# lab3.net
KiCad netlist of a schematic drawn in EAGLE
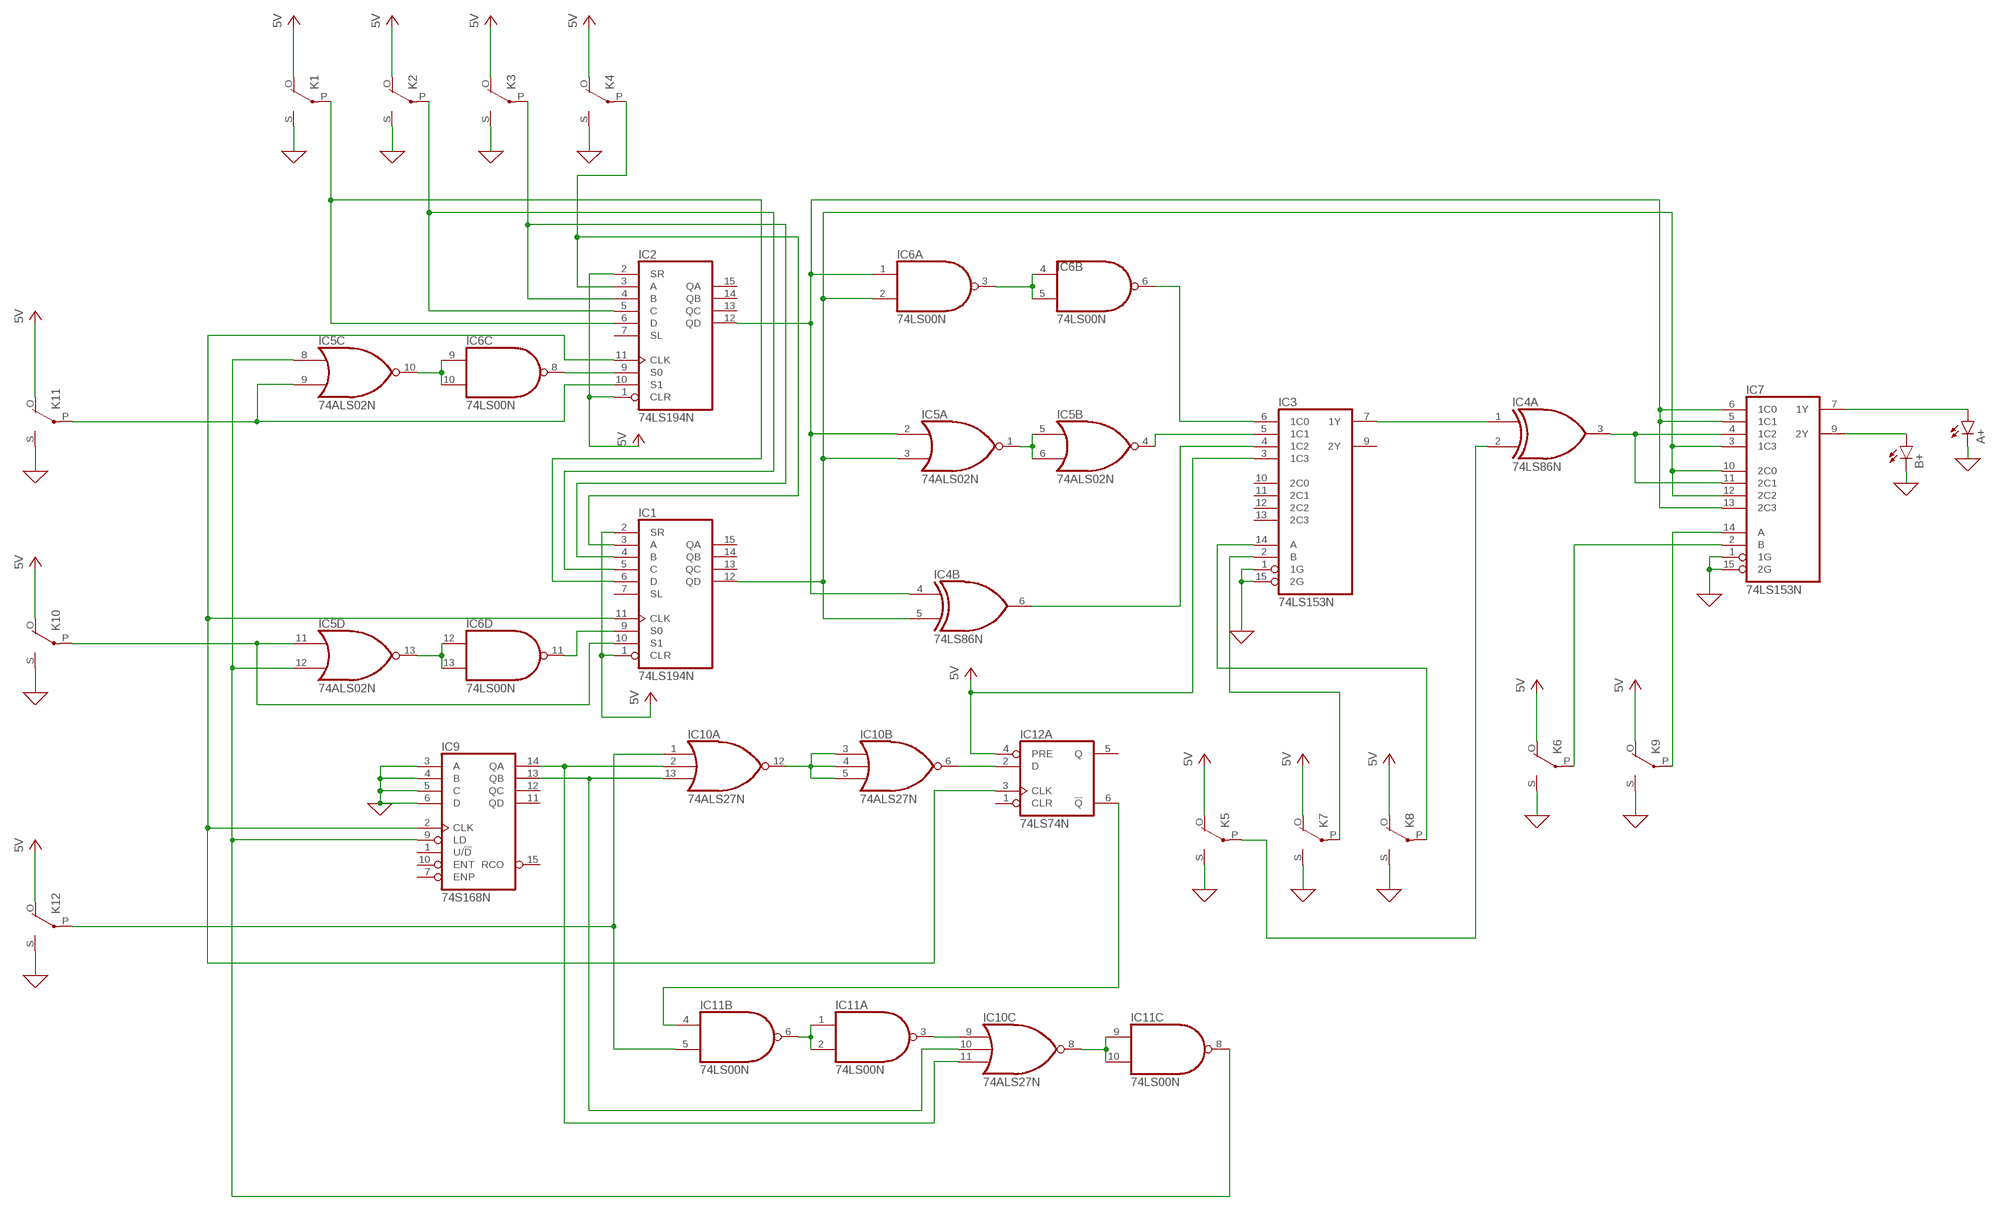
[diagram p0: schematic, sheet 1]

(export (version "E")
  (design (tool "Eeschema 10.0.6"))
  (components
    (comp (ref "A+")
      (value "LED3MM")
      (footprint "eagle-import:LED3MM")
      (libsource (lib "eagle-import") (part "LED3MM"))
    )
    (comp (ref "B+")
      (value "LED3MM")
      (footprint "eagle-import:LED3MM")
      (libsource (lib "eagle-import") (part "LED3MM"))
    )
    (comp (ref "IC1")
      (value "74LS194N")
      (footprint "eagle-import:DIL16")
      (libsource (lib "eagle-import") (part "74194NLS"))
    )
    (comp (ref "IC2")
      (value "74LS194N")
      (footprint "eagle-import:DIL16")
      (libsource (lib "eagle-import") (part "74194NLS"))
    )
    (comp (ref "IC3")
      (value "74LS153N")
      (footprint "eagle-import:DIL16")
      (libsource (lib "eagle-import") (part "74153NLS"))
    )
    (comp (ref "IC4")
      (value "74LS86N")
      (footprint "eagle-import:DIL14")
      (libsource (lib "eagle-import") (part "7486NLS"))
    )
    (comp (ref "IC5")
      (value "74ALS02N")
      (footprint "eagle-import:DIL14")
      (libsource (lib "eagle-import") (part "7402NALS"))
    )
    (comp (ref "IC6")
      (value "74LS00N")
      (footprint "eagle-import:DIL14")
      (libsource (lib "eagle-import") (part "7400NLS"))
    )
    (comp (ref "IC7")
      (value "74LS153N")
      (footprint "eagle-import:DIL16")
      (libsource (lib "eagle-import") (part "74153NLS"))
    )
    (comp (ref "IC9")
      (value "74S168N")
      (footprint "eagle-import:DIL16")
      (libsource (lib "eagle-import") (part "74168NS"))
    )
    (comp (ref "IC10")
      (value "74ALS27N")
      (footprint "eagle-import:DIL14")
      (libsource (lib "eagle-import") (part "7427NALS"))
    )
    (comp (ref "IC11")
      (value "74LS00N")
      (footprint "eagle-import:DIL14")
      (libsource (lib "eagle-import") (part "7400NLS"))
    )
    (comp (ref "IC12")
      (value "74LS74N")
      (footprint "eagle-import:DIL14")
      (libsource (lib "eagle-import") (part "7474NLS"))
    )
    (comp (ref "K1")
      (value "E3206L")
      (footprint "eagle-import:E3206L")
      (libsource (lib "eagle-import") (part "E3206L"))
    )
    (comp (ref "K2")
      (value "E3206L")
      (footprint "eagle-import:E3206L")
      (libsource (lib "eagle-import") (part "E3206L"))
    )
    (comp (ref "K3")
      (value "E3206L")
      (footprint "eagle-import:E3206L")
      (libsource (lib "eagle-import") (part "E3206L"))
    )
    (comp (ref "K4")
      (value "E3206L")
      (footprint "eagle-import:E3206L")
      (libsource (lib "eagle-import") (part "E3206L"))
    )
    (comp (ref "K5")
      (value "E3206L")
      (footprint "eagle-import:E3206L")
      (libsource (lib "eagle-import") (part "E3206L"))
    )
    (comp (ref "K6")
      (value "E3206L")
      (footprint "eagle-import:E3206L")
      (libsource (lib "eagle-import") (part "E3206L"))
    )
    (comp (ref "K7")
      (value "E3206L")
      (footprint "eagle-import:E3206L")
      (libsource (lib "eagle-import") (part "E3206L"))
    )
    (comp (ref "K8")
      (value "E3206L")
      (footprint "eagle-import:E3206L")
      (libsource (lib "eagle-import") (part "E3206L"))
    )
    (comp (ref "K9")
      (value "E3206L")
      (footprint "eagle-import:E3206L")
      (libsource (lib "eagle-import") (part "E3206L"))
    )
    (comp (ref "K10")
      (value "E3206L")
      (footprint "eagle-import:E3206L")
      (libsource (lib "eagle-import") (part "E3206L"))
    )
    (comp (ref "K11")
      (value "E3206L")
      (footprint "eagle-import:E3206L")
      (libsource (lib "eagle-import") (part "E3206L"))
    )
    (comp (ref "K12")
      (value "E3206L")
      (footprint "eagle-import:E3206L")
      (libsource (lib "eagle-import") (part "E3206L"))
    )
  )
  (nets
    (net (code "1") (name "5V") (class "Default")
      (node (ref "IC1") (pin "1") (pinfunction "CLR_1") (pintype "input"))
      (node (ref "IC1") (pin "2") (pinfunction "SR_2") (pintype "input"))
      (node (ref "IC12") (pin "4") (pinfunction "PRE_4") (pintype "input"))
      (node (ref "IC2") (pin "1") (pinfunction "CLR_1") (pintype "input"))
      (node (ref "IC2") (pin "2") (pinfunction "SR_2") (pintype "input"))
      (node (ref "IC3") (pin "3") (pinfunction "1C3_3") (pintype "input"))
      (node (ref "K1") (pin "O") (pinfunction "O_O") (pintype "passive"))
      (node (ref "K10") (pin "O") (pinfunction "O_O") (pintype "passive"))
      (node (ref "K11") (pin "O") (pinfunction "O_O") (pintype "passive"))
      (node (ref "K12") (pin "O") (pinfunction "O_O") (pintype "passive"))
      (node (ref "K2") (pin "O") (pinfunction "O_O") (pintype "passive"))
      (node (ref "K3") (pin "O") (pinfunction "O_O") (pintype "passive"))
      (node (ref "K4") (pin "O") (pinfunction "O_O") (pintype "passive"))
      (node (ref "K5") (pin "O") (pinfunction "O_O") (pintype "passive"))
      (node (ref "K6") (pin "O") (pinfunction "O_O") (pintype "passive"))
      (node (ref "K7") (pin "O") (pinfunction "O_O") (pintype "passive"))
      (node (ref "K8") (pin "O") (pinfunction "O_O") (pintype "passive"))
      (node (ref "K9") (pin "O") (pinfunction "O_O") (pintype "passive"))
    )
    (net (code "2") (name "GND") (class "Default")
      (node (ref "A+") (pin "K") (pinfunction "C_K") (pintype "passive"))
      (node (ref "B+") (pin "K") (pinfunction "C_K") (pintype "passive"))
      (node (ref "IC3") (pin "1") (pinfunction "1G_1") (pintype "input"))
      (node (ref "IC3") (pin "15") (pinfunction "2G_15") (pintype "input"))
      (node (ref "IC7") (pin "1") (pinfunction "1G_1") (pintype "input"))
      (node (ref "IC7") (pin "15") (pinfunction "2G_15") (pintype "input"))
      (node (ref "IC9") (pin "3") (pinfunction "A_3") (pintype "input"))
      (node (ref "IC9") (pin "4") (pinfunction "B_4") (pintype "input"))
      (node (ref "IC9") (pin "5") (pinfunction "C_5") (pintype "input"))
      (node (ref "IC9") (pin "6") (pinfunction "D_6") (pintype "input"))
      (node (ref "K1") (pin "S") (pinfunction "S_S") (pintype "passive"))
      (node (ref "K10") (pin "S") (pinfunction "S_S") (pintype "passive"))
      (node (ref "K11") (pin "S") (pinfunction "S_S") (pintype "passive"))
      (node (ref "K12") (pin "S") (pinfunction "S_S") (pintype "passive"))
      (node (ref "K2") (pin "S") (pinfunction "S_S") (pintype "passive"))
      (node (ref "K3") (pin "S") (pinfunction "S_S") (pintype "passive"))
      (node (ref "K4") (pin "S") (pinfunction "S_S") (pintype "passive"))
      (node (ref "K5") (pin "S") (pinfunction "S_S") (pintype "passive"))
      (node (ref "K6") (pin "S") (pinfunction "S_S") (pintype "passive"))
      (node (ref "K7") (pin "S") (pinfunction "S_S") (pintype "passive"))
      (node (ref "K8") (pin "S") (pinfunction "S_S") (pintype "passive"))
      (node (ref "K9") (pin "S") (pinfunction "S_S") (pintype "passive"))
    )
    (net (code "3") (name "Net-(IC1A-A)") (class "Default")
      (node (ref "IC1") (pin "3") (pinfunction "A_3") (pintype "input"))
      (node (ref "IC2") (pin "3") (pinfunction "A_3") (pintype "input"))
      (node (ref "K4") (pin "P") (pinfunction "P_P") (pintype "passive"))
    )
    (net (code "4") (name "Net-(IC1A-B)") (class "Default")
      (node (ref "IC1") (pin "4") (pinfunction "B_4") (pintype "input"))
      (node (ref "IC2") (pin "4") (pinfunction "B_4") (pintype "input"))
      (node (ref "K3") (pin "P") (pinfunction "P_P") (pintype "passive"))
    )
    (net (code "5") (name "Net-(IC1A-C)") (class "Default")
      (node (ref "IC1") (pin "5") (pinfunction "C_5") (pintype "input"))
      (node (ref "IC2") (pin "5") (pinfunction "C_5") (pintype "input"))
      (node (ref "K2") (pin "P") (pinfunction "P_P") (pintype "passive"))
    )
    (net (code "6") (name "Net-(IC1A-D)") (class "Default")
      (node (ref "IC1") (pin "6") (pinfunction "D_6") (pintype "input"))
      (node (ref "IC2") (pin "6") (pinfunction "D_6") (pintype "input"))
      (node (ref "K1") (pin "P") (pinfunction "P_P") (pintype "passive"))
    )
    (net (code "7") (name "Net-(IC1A-QD)") (class "Default")
      (node (ref "IC1") (pin "12") (pinfunction "QD_12") (pintype "output"))
      (node (ref "IC4") (pin "5") (pinfunction "I1_5") (pintype "input"))
      (node (ref "IC5") (pin "3") (pinfunction "I1_3") (pintype "input"))
      (node (ref "IC6") (pin "2") (pinfunction "I1_2") (pintype "input"))
      (node (ref "IC7") (pin "10") (pinfunction "2C0_10") (pintype "input"))
      (node (ref "IC7") (pin "12") (pinfunction "2C2_12") (pintype "input"))
      (node (ref "IC7") (pin "3") (pinfunction "1C3_3") (pintype "input"))
    )
    (net (code "8") (name "Net-(IC1A-S0)") (class "Default")
      (node (ref "IC1") (pin "9") (pinfunction "S0_9") (pintype "input"))
      (node (ref "IC6") (pin "11") (pinfunction "O_11") (pintype "output"))
    )
    (net (code "9") (name "Net-(IC1A-S1)") (class "Default")
      (node (ref "IC1") (pin "10") (pinfunction "S1_10") (pintype "input"))
      (node (ref "IC5") (pin "11") (pinfunction "I0_11") (pintype "input"))
      (node (ref "K10") (pin "P") (pinfunction "P_P") (pintype "passive"))
    )
    (net (code "10") (name "Net-(IC2A-QD)") (class "Default")
      (node (ref "IC2") (pin "12") (pinfunction "QD_12") (pintype "output"))
      (node (ref "IC4") (pin "4") (pinfunction "I0_4") (pintype "input"))
      (node (ref "IC5") (pin "2") (pinfunction "I0_2") (pintype "input"))
      (node (ref "IC6") (pin "1") (pinfunction "I0_1") (pintype "input"))
      (node (ref "IC7") (pin "13") (pinfunction "2C3_13") (pintype "input"))
      (node (ref "IC7") (pin "5") (pinfunction "1C1_5") (pintype "input"))
      (node (ref "IC7") (pin "6") (pinfunction "1C0_6") (pintype "input"))
    )
    (net (code "11") (name "Net-(IC2A-S0)") (class "Default")
      (node (ref "IC2") (pin "9") (pinfunction "S0_9") (pintype "input"))
      (node (ref "IC6") (pin "8") (pinfunction "O_8") (pintype "output"))
    )
    (net (code "12") (name "Net-(IC2A-S1)") (class "Default")
      (node (ref "IC2") (pin "10") (pinfunction "S1_10") (pintype "input"))
      (node (ref "IC5") (pin "9") (pinfunction "I1_9") (pintype "input"))
      (node (ref "K11") (pin "P") (pinfunction "P_P") (pintype "passive"))
    )
    (net (code "13") (name "Net-(IC3A-1C0)") (class "Default")
      (node (ref "IC3") (pin "6") (pinfunction "1C0_6") (pintype "input"))
      (node (ref "IC6") (pin "6") (pinfunction "O_6") (pintype "output"))
    )
    (net (code "14") (name "Net-(IC3A-1C1)") (class "Default")
      (node (ref "IC3") (pin "5") (pinfunction "1C1_5") (pintype "input"))
      (node (ref "IC5") (pin "4") (pinfunction "O_4") (pintype "output"))
    )
    (net (code "15") (name "Net-(IC3A-1C2)") (class "Default")
      (node (ref "IC3") (pin "4") (pinfunction "1C2_4") (pintype "input"))
      (node (ref "IC4") (pin "6") (pinfunction "O_6") (pintype "output"))
    )
    (net (code "16") (name "Net-(IC3A-1Y)") (class "Default")
      (node (ref "IC3") (pin "7") (pinfunction "1Y_7") (pintype "output"))
      (node (ref "IC4") (pin "1") (pinfunction "I0_1") (pintype "input"))
    )
    (net (code "17") (name "Net-(IC3A-A)") (class "Default")
      (node (ref "IC3") (pin "14") (pinfunction "A_14") (pintype "input"))
      (node (ref "K8") (pin "P") (pinfunction "P_P") (pintype "passive"))
    )
    (net (code "18") (name "Net-(IC3A-B)") (class "Default")
      (node (ref "IC3") (pin "2") (pinfunction "B_2") (pintype "input"))
      (node (ref "K7") (pin "P") (pinfunction "P_P") (pintype "passive"))
    )
    (net (code "19") (name "Net-(IC4A-I1)") (class "Default")
      (node (ref "IC4") (pin "2") (pinfunction "I1_2") (pintype "input"))
      (node (ref "K5") (pin "P") (pinfunction "P_P") (pintype "passive"))
    )
    (net (code "20") (name "Net-(IC4A-O)") (class "Default")
      (node (ref "IC4") (pin "3") (pinfunction "O_3") (pintype "output"))
      (node (ref "IC7") (pin "11") (pinfunction "2C1_11") (pintype "input"))
      (node (ref "IC7") (pin "4") (pinfunction "1C2_4") (pintype "input"))
    )
    (net (code "21") (name "Net-(IC5A-O)") (class "Default")
      (node (ref "IC5") (pin "1") (pinfunction "O_1") (pintype "output"))
      (node (ref "IC5") (pin "5") (pinfunction "I0_5") (pintype "input"))
      (node (ref "IC5") (pin "6") (pinfunction "I1_6") (pintype "input"))
    )
    (net (code "22") (name "Net-(IC5C-O)") (class "Default")
      (node (ref "IC5") (pin "10") (pinfunction "O_10") (pintype "output"))
      (node (ref "IC6") (pin "10") (pinfunction "I1_10") (pintype "input"))
      (node (ref "IC6") (pin "9") (pinfunction "I0_9") (pintype "input"))
    )
    (net (code "23") (name "Net-(IC5D-O)") (class "Default")
      (node (ref "IC5") (pin "13") (pinfunction "O_13") (pintype "output"))
      (node (ref "IC6") (pin "12") (pinfunction "I0_12") (pintype "input"))
      (node (ref "IC6") (pin "13") (pinfunction "I1_13") (pintype "input"))
    )
    (net (code "24") (name "Net-(IC6A-O)") (class "Default")
      (node (ref "IC6") (pin "3") (pinfunction "O_3") (pintype "output"))
      (node (ref "IC6") (pin "4") (pinfunction "I0_4") (pintype "input"))
      (node (ref "IC6") (pin "5") (pinfunction "I1_5") (pintype "input"))
    )
    (net (code "25") (name "Net-(IC7A-1Y)") (class "Default")
      (node (ref "A+") (pin "A") (pinfunction "A_A") (pintype "passive"))
      (node (ref "IC7") (pin "7") (pinfunction "1Y_7") (pintype "output"))
    )
    (net (code "26") (name "Net-(IC7A-2Y)") (class "Default")
      (node (ref "B+") (pin "A") (pinfunction "A_A") (pintype "passive"))
      (node (ref "IC7") (pin "9") (pinfunction "2Y_9") (pintype "output"))
    )
    (net (code "27") (name "Net-(IC7A-A)") (class "Default")
      (node (ref "IC7") (pin "14") (pinfunction "A_14") (pintype "input"))
      (node (ref "K9") (pin "P") (pinfunction "P_P") (pintype "passive"))
    )
    (net (code "28") (name "Net-(IC7A-B)") (class "Default")
      (node (ref "IC7") (pin "2") (pinfunction "B_2") (pintype "input"))
      (node (ref "K6") (pin "P") (pinfunction "P_P") (pintype "passive"))
    )
    (net (code "29") (name "Net-(IC10A-I0)") (class "Default")
      (node (ref "IC10") (pin "1") (pinfunction "I0_1") (pintype "input"))
      (node (ref "IC11") (pin "5") (pinfunction "I1_5") (pintype "input"))
      (node (ref "K12") (pin "P") (pinfunction "P_P") (pintype "passive"))
    )
    (net (code "30") (name "Net-(IC10A-I1)") (class "Default")
      (node (ref "IC10") (pin "11") (pinfunction "I2_11") (pintype "input"))
      (node (ref "IC10") (pin "2") (pinfunction "I1_2") (pintype "input"))
      (node (ref "IC9") (pin "14") (pinfunction "QA_14") (pintype "output"))
    )
    (net (code "31") (name "Net-(IC10A-I2)") (class "Default")
      (node (ref "IC10") (pin "10") (pinfunction "I1_10") (pintype "input"))
      (node (ref "IC10") (pin "13") (pinfunction "I2_13") (pintype "input"))
      (node (ref "IC9") (pin "13") (pinfunction "QB_13") (pintype "output"))
    )
    (net (code "32") (name "Net-(IC10A-O)") (class "Default")
      (node (ref "IC10") (pin "12") (pinfunction "O_12") (pintype "output"))
      (node (ref "IC10") (pin "3") (pinfunction "I0_3") (pintype "input"))
      (node (ref "IC10") (pin "4") (pinfunction "I1_4") (pintype "input"))
      (node (ref "IC10") (pin "5") (pinfunction "I2_5") (pintype "input"))
    )
    (net (code "33") (name "Net-(IC10B-O)") (class "Default")
      (node (ref "IC10") (pin "6") (pinfunction "O_6") (pintype "output"))
      (node (ref "IC12") (pin "2") (pinfunction "D_2") (pintype "input"))
    )
    (net (code "34") (name "Net-(IC10C-I0)") (class "Default")
      (node (ref "IC10") (pin "9") (pinfunction "I0_9") (pintype "input"))
      (node (ref "IC11") (pin "3") (pinfunction "O_3") (pintype "output"))
    )
    (net (code "35") (name "Net-(IC10C-O)") (class "Default")
      (node (ref "IC10") (pin "8") (pinfunction "O_8") (pintype "output"))
      (node (ref "IC11") (pin "10") (pinfunction "I1_10") (pintype "input"))
      (node (ref "IC11") (pin "9") (pinfunction "I0_9") (pintype "input"))
    )
    (net (code "36") (name "Net-(IC11A-I0)") (class "Default")
      (node (ref "IC11") (pin "1") (pinfunction "I0_1") (pintype "input"))
      (node (ref "IC11") (pin "2") (pinfunction "I1_2") (pintype "input"))
      (node (ref "IC11") (pin "6") (pinfunction "O_6") (pintype "output"))
    )
    (net (code "37") (name "Net-(IC11B-I0)") (class "Default")
      (node (ref "IC11") (pin "4") (pinfunction "I0_4") (pintype "input"))
      (node (ref "IC12") (pin "6") (pinfunction "~{Q}_6") (pintype "output"))
    )
    (net (code "38") (name "Net-(IC11C-O)") (class "Default")
      (node (ref "IC11") (pin "8") (pinfunction "O_8") (pintype "output"))
      (node (ref "IC5") (pin "12") (pinfunction "I1_12") (pintype "input"))
      (node (ref "IC5") (pin "8") (pinfunction "I0_8") (pintype "input"))
      (node (ref "IC9") (pin "9") (pinfunction "LD_9") (pintype "input"))
    )
    (net (code "39") (name "Net-(IC12A-CLK)") (class "Default")
      (node (ref "IC1") (pin "11") (pinfunction "CLK_11") (pintype "input"))
      (node (ref "IC12") (pin "3") (pinfunction "CLK_3") (pintype "input"))
      (node (ref "IC2") (pin "11") (pinfunction "CLK_11") (pintype "input"))
      (node (ref "IC9") (pin "2") (pinfunction "CLK_2") (pintype "input"))
    )
    (net (code "40") (name "unconnected-(IC1A-QA-Pad15)") (class "Default")
      (node (ref "IC1") (pin "15") (pinfunction "QA_15") (pintype "output"))
    )
    (net (code "41") (name "unconnected-(IC1A-QB-Pad14)") (class "Default")
      (node (ref "IC1") (pin "14") (pinfunction "QB_14") (pintype "output"))
    )
    (net (code "42") (name "unconnected-(IC1A-QC-Pad13)") (class "Default")
      (node (ref "IC1") (pin "13") (pinfunction "QC_13") (pintype "output"))
    )
    (net (code "43") (name "unconnected-(IC1A-SL-Pad7)") (class "Default")
      (node (ref "IC1") (pin "7") (pinfunction "SL_7") (pintype "input"))
    )
    (net (code "44") (name "unconnected-(IC2A-QA-Pad15)") (class "Default")
      (node (ref "IC2") (pin "15") (pinfunction "QA_15") (pintype "output"))
    )
    (net (code "45") (name "unconnected-(IC2A-QB-Pad14)") (class "Default")
      (node (ref "IC2") (pin "14") (pinfunction "QB_14") (pintype "output"))
    )
    (net (code "46") (name "unconnected-(IC2A-QC-Pad13)") (class "Default")
      (node (ref "IC2") (pin "13") (pinfunction "QC_13") (pintype "output"))
    )
    (net (code "47") (name "unconnected-(IC2A-SL-Pad7)") (class "Default")
      (node (ref "IC2") (pin "7") (pinfunction "SL_7") (pintype "input"))
    )
    (net (code "48") (name "unconnected-(IC3A-2C0-Pad10)") (class "Default")
      (node (ref "IC3") (pin "10") (pinfunction "2C0_10") (pintype "input"))
    )
    (net (code "49") (name "unconnected-(IC3A-2C1-Pad11)") (class "Default")
      (node (ref "IC3") (pin "11") (pinfunction "2C1_11") (pintype "input"))
    )
    (net (code "50") (name "unconnected-(IC3A-2C2-Pad12)") (class "Default")
      (node (ref "IC3") (pin "12") (pinfunction "2C2_12") (pintype "input"))
    )
    (net (code "51") (name "unconnected-(IC3A-2C3-Pad13)") (class "Default")
      (node (ref "IC3") (pin "13") (pinfunction "2C3_13") (pintype "input"))
    )
    (net (code "52") (name "unconnected-(IC3A-2Y-Pad9)") (class "Default")
      (node (ref "IC3") (pin "9") (pinfunction "2Y_9") (pintype "output"))
    )
    (net (code "53") (name "unconnected-(IC9A-ENP-Pad7)") (class "Default")
      (node (ref "IC9") (pin "7") (pinfunction "ENP_7") (pintype "input"))
    )
    (net (code "54") (name "unconnected-(IC9A-ENT-Pad10)") (class "Default")
      (node (ref "IC9") (pin "10") (pinfunction "ENT_10") (pintype "input"))
    )
    (net (code "55") (name "unconnected-(IC9A-QC-Pad12)") (class "Default")
      (node (ref "IC9") (pin "12") (pinfunction "QC_12") (pintype "output"))
    )
    (net (code "56") (name "unconnected-(IC9A-QD-Pad11)") (class "Default")
      (node (ref "IC9") (pin "11") (pinfunction "QD_11") (pintype "output"))
    )
    (net (code "57") (name "unconnected-(IC9A-RCO-Pad15)") (class "Default")
      (node (ref "IC9") (pin "15") (pinfunction "RCO_15") (pintype "output"))
    )
    (net (code "58") (name "unconnected-(IC9A-U{slash}~{D}-Pad1)") (class "Default")
      (node (ref "IC9") (pin "1") (pinfunction "U/~{D}_1") (pintype "input"))
    )
    (net (code "59") (name "unconnected-(IC12A-CLR-Pad1)") (class "Default")
      (node (ref "IC12") (pin "1") (pinfunction "CLR_1") (pintype "input"))
    )
    (net (code "60") (name "unconnected-(IC12A-Q-Pad5)") (class "Default")
      (node (ref "IC12") (pin "5") (pinfunction "Q_5") (pintype "output"))
    )
  )
)
